# E-01-MB.net
KiCad netlist of a schematic drawn in Altium Designer
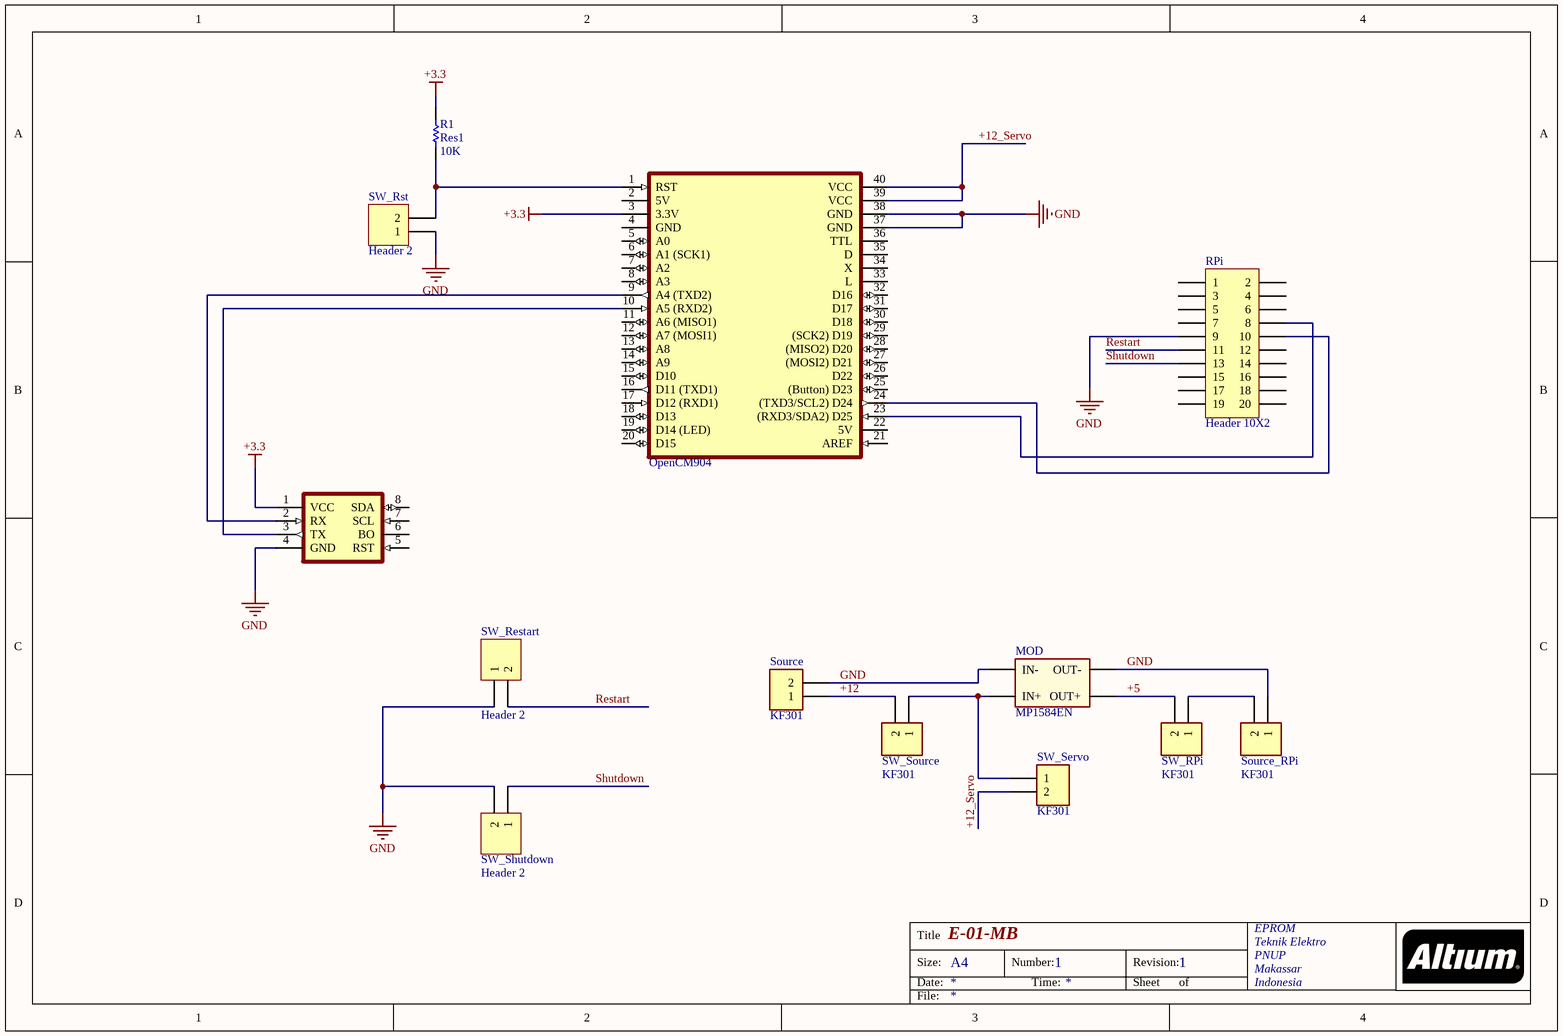
[diagram p0: E-01-MB.SchDoc]

(export (version "E")
  (design (tool "Eeschema 10.0.6"))
  (components
    (comp (ref "GY-Sensor")
      (value "GY25")
      (footprint "GY25")
      (libsource (lib "E-01-MB_Schlib") (part "GY25"))
    )
    (comp (ref "Main")
      (value "OpenCM904")
      (footprint "OpenCM904-DIP40")
      (libsource (lib "E-01-MB_Schlib") (part "OpenCM904"))
    )
    (comp (ref "MOD")
      (value "MP1584EN")
      (footprint "PCBComponent_1")
      (libsource (lib "E-01-PDB_Schlib") (part "MP1584EN"))
    )
    (comp (ref "R1")
      (value "Res1")
      (footprint "AXIAL-0.3")
      (description "Resistor")
      (fields (field (name "ALTIUM_VALUE") "10K") (field (name "PUBLISHER") "Altium Limited"))
      (libsource (lib "Miscellaneous Devices") (part "Res1"))
    )
    (comp (ref "RPi")
      (value "Header 10X2")
      (footprint "HDR2X10")
      (description "Header, 10-Pin, Dual row")
      (fields (field (name "PUBLISHER") "Altium Limited"))
      (libsource (lib "Miscellaneous Connectors") (part "Header 10X2"))
    )
    (comp (ref "Source")
      (value "KF301")
      (footprint "KF301")
      (libsource (lib "E-01-MB_Schlib") (part "KF301"))
    )
    (comp (ref "Source_RPi") (value "KF301") (footprint "KF301") (libsource (lib "") (part "KF301_1")))
    (comp (ref "SW_Restart")
      (value "Header 2")
      (footprint "HDR1X2")
      (description "Header, 2-Pin")
      (fields (field (name "PUBLISHER") "Altium Limited"))
      (libsource (lib "") (part "Header 2_2"))
    )
    (comp (ref "SW_RPi") (value "KF301") (footprint "KF301") (libsource (lib "") (part "KF301_1")))
    (comp (ref "SW_Rst")
      (value "Header 2")
      (footprint "HDR1X2")
      (description "Header, 2-Pin")
      (fields (field (name "PUBLISHER") "Altium Limited"))
      (libsource (lib "Miscellaneous Connectors") (part "Header 2"))
    )
    (comp (ref "SW_Servo") (value "KF301") (footprint "KF301") (libsource (lib "") (part "KF301_2")))
    (comp (ref "SW_Shutdown")
      (value "Header 2")
      (footprint "HDR1X2")
      (description "Header, 2-Pin")
      (fields (field (name "PUBLISHER") "Altium Limited"))
      (libsource (lib "") (part "Header 2_1"))
    )
    (comp (ref "SW_Source") (value "KF301") (footprint "KF301") (libsource (lib "") (part "KF301_1")))
  )
  (nets
    (net (code "1") (name "+3.3") (class "Default")
      (node (ref "GY-Sensor") (pin "1") (pinfunction "VCC_1") (pintype "power_in"))
      (node (ref "Main") (pin "3") (pinfunction "3.3V_3") (pintype "power_in"))
      (node (ref "R1") (pin "2") (pinfunction "2_2") (pintype "passive"))
    )
    (net (code "2") (name "/+5") (class "Default")
      (node (ref "MOD") (pin "4") (pinfunction "OUT+_4") (pintype "power_in"))
      (node (ref "SW_RPi") (pin "2") (pinfunction "2_2") (pintype "passive"))
    )
    (net (code "3") (name "/+12") (class "Default")
      (node (ref "SW_Source") (pin "2") (pinfunction "2_2") (pintype "passive"))
      (node (ref "Source") (pin "1") (pinfunction "1_1") (pintype "passive"))
    )
    (net (code "4") (name "/+12_Servo") (class "Default")
      (node (ref "Main") (pin "39") (pinfunction "VCC_39") (pintype "power_in"))
      (node (ref "Main") (pin "40") (pinfunction "VCC_40") (pintype "power_in"))
      (node (ref "SW_Servo") (pin "2") (pinfunction "2_2") (pintype "passive"))
    )
    (net (code "5") (name "/Restart") (class "Default")
      (node (ref "RPi") (pin "11") (pinfunction "11_11") (pintype "passive"))
      (node (ref "SW_Restart") (pin "2") (pinfunction "2_2") (pintype "passive"))
    )
    (net (code "6") (name "/Shutdown") (class "Default")
      (node (ref "RPi") (pin "13") (pinfunction "13_13") (pintype "passive"))
      (node (ref "SW_Shutdown") (pin "1") (pinfunction "1_1") (pintype "passive"))
    )
    (net (code "7") (name "GND") (class "Default")
      (node (ref "GY-Sensor") (pin "4") (pinfunction "GND_4") (pintype "power_in"))
      (node (ref "MOD") (pin "1") (pinfunction "IN-_1") (pintype "power_in"))
      (node (ref "MOD") (pin "3") (pinfunction "OUT-_3") (pintype "power_in"))
      (node (ref "Main") (pin "37") (pinfunction "GND_37") (pintype "power_in"))
      (node (ref "Main") (pin "38") (pinfunction "GND_38") (pintype "power_in"))
      (node (ref "RPi") (pin "9") (pinfunction "9_9") (pintype "passive"))
      (node (ref "SW_Restart") (pin "1") (pinfunction "1_1") (pintype "passive"))
      (node (ref "SW_Rst") (pin "1") (pinfunction "1_1") (pintype "passive"))
      (node (ref "SW_Shutdown") (pin "2") (pinfunction "2_2") (pintype "passive"))
      (node (ref "Source") (pin "2") (pinfunction "2_2") (pintype "passive"))
      (node (ref "Source_RPi") (pin "1") (pinfunction "1_1") (pintype "passive"))
    )
    (net (code "8") (name "Net-(GY-Sensor-RX)") (class "Default")
      (node (ref "GY-Sensor") (pin "2") (pinfunction "RX_2") (pintype "input"))
      (node (ref "Main") (pin "9") (pinfunction "A4_(TXD2)_9") (pintype "output"))
    )
    (net (code "9") (name "Net-(GY-Sensor-TX)") (class "Default")
      (node (ref "GY-Sensor") (pin "3") (pinfunction "TX_3") (pintype "output"))
      (node (ref "Main") (pin "10") (pinfunction "A5_(RXD2)_10") (pintype "input"))
    )
    (net (code "10") (name "Net-(MOD-IN+)") (class "Default")
      (node (ref "MOD") (pin "2") (pinfunction "IN+_2") (pintype "power_in"))
      (node (ref "SW_Servo") (pin "1") (pinfunction "1_1") (pintype "passive"))
      (node (ref "SW_Source") (pin "1") (pinfunction "1_1") (pintype "passive"))
    )
    (net (code "11") (name "Net-(Main-(RXD3{slash}SDA2)_D25)") (class "Default")
      (node (ref "Main") (pin "23") (pinfunction "(RXD3/SDA2)_D25_23") (pintype "input"))
      (node (ref "RPi") (pin "8") (pinfunction "8_8") (pintype "passive"))
    )
    (net (code "12") (name "Net-(Main-(TXD3{slash}SCL2)_D24)") (class "Default")
      (node (ref "Main") (pin "24") (pinfunction "(TXD3/SCL2)_D24_24") (pintype "output"))
      (node (ref "RPi") (pin "10") (pinfunction "10_10") (pintype "passive"))
    )
    (net (code "13") (name "Net-(Main-RST)") (class "Default")
      (node (ref "Main") (pin "1") (pinfunction "RST_1") (pintype "input"))
      (node (ref "R1") (pin "1") (pinfunction "1_1") (pintype "passive"))
      (node (ref "SW_Rst") (pin "2") (pinfunction "2_2") (pintype "passive"))
    )
    (net (code "14") (name "Net-(SW_RPi-Pad1)") (class "Default")
      (node (ref "SW_RPi") (pin "1") (pinfunction "1_1") (pintype "passive"))
      (node (ref "Source_RPi") (pin "2") (pinfunction "2_2") (pintype "passive"))
    )
    (net (code "15") (name "unconnected-(GY-Sensor-BO-Pad6)") (class "Default")
      (node (ref "GY-Sensor") (pin "6") (pinfunction "BO_6") (pintype "passive"))
    )
    (net (code "16") (name "unconnected-(GY-Sensor-RST-Pad5)") (class "Default")
      (node (ref "GY-Sensor") (pin "5") (pinfunction "RST_5") (pintype "input"))
    )
    (net (code "17") (name "unconnected-(GY-Sensor-SCL-Pad7)") (class "Default")
      (node (ref "GY-Sensor") (pin "7") (pinfunction "SCL_7") (pintype "input"))
    )
    (net (code "18") (name "unconnected-(GY-Sensor-SDA-Pad8)") (class "Default")
      (node (ref "GY-Sensor") (pin "8") (pinfunction "SDA_8") (pintype "bidirectional"))
    )
    (net (code "19") (name "unconnected-(Main-(Button)_D23-Pad25)") (class "Default")
      (node (ref "Main") (pin "25") (pinfunction "(Button)_D23_25") (pintype "bidirectional"))
    )
    (net (code "20") (name "unconnected-(Main-(MISO2)_D20-Pad28)") (class "Default")
      (node (ref "Main") (pin "28") (pinfunction "(MISO2)_D20_28") (pintype "bidirectional"))
    )
    (net (code "21") (name "unconnected-(Main-(MOSI2)_D21-Pad27)") (class "Default")
      (node (ref "Main") (pin "27") (pinfunction "(MOSI2)_D21_27") (pintype "bidirectional"))
    )
    (net (code "22") (name "unconnected-(Main-(SCK2)_D19-Pad29)") (class "Default")
      (node (ref "Main") (pin "29") (pinfunction "(SCK2)_D19_29") (pintype "bidirectional"))
    )
    (net (code "23") (name "unconnected-(Main-5V-Pad2)") (class "Default")
      (node (ref "Main") (pin "2") (pinfunction "5V_2") (pintype "power_in"))
    )
    (net (code "24") (name "unconnected-(Main-5V-Pad22)") (class "Default")
      (node (ref "Main") (pin "22") (pinfunction "5V_22") (pintype "power_in"))
    )
    (net (code "25") (name "unconnected-(Main-A0-Pad5)") (class "Default")
      (node (ref "Main") (pin "5") (pinfunction "A0_5") (pintype "bidirectional"))
    )
    (net (code "26") (name "unconnected-(Main-A1_(SCK1)-Pad6)") (class "Default")
      (node (ref "Main") (pin "6") (pinfunction "A1_(SCK1)_6") (pintype "bidirectional"))
    )
    (net (code "27") (name "unconnected-(Main-A2-Pad7)") (class "Default")
      (node (ref "Main") (pin "7") (pinfunction "A2_7") (pintype "bidirectional"))
    )
    (net (code "28") (name "unconnected-(Main-A3-Pad8)") (class "Default")
      (node (ref "Main") (pin "8") (pinfunction "A3_8") (pintype "bidirectional"))
    )
    (net (code "29") (name "unconnected-(Main-A6_(MISO1)-Pad11)") (class "Default")
      (node (ref "Main") (pin "11") (pinfunction "A6_(MISO1)_11") (pintype "bidirectional"))
    )
    (net (code "30") (name "unconnected-(Main-A7_(MOSI1)-Pad12)") (class "Default")
      (node (ref "Main") (pin "12") (pinfunction "A7_(MOSI1)_12") (pintype "bidirectional"))
    )
    (net (code "31") (name "unconnected-(Main-A8-Pad13)") (class "Default")
      (node (ref "Main") (pin "13") (pinfunction "A8_13") (pintype "bidirectional"))
    )
    (net (code "32") (name "unconnected-(Main-A9-Pad14)") (class "Default")
      (node (ref "Main") (pin "14") (pinfunction "A9_14") (pintype "bidirectional"))
    )
    (net (code "33") (name "unconnected-(Main-AREF-Pad21)") (class "Default")
      (node (ref "Main") (pin "21") (pinfunction "AREF_21") (pintype "input"))
    )
    (net (code "34") (name "unconnected-(Main-D-Pad35)") (class "Default")
      (node (ref "Main") (pin "35") (pinfunction "D_35") (pintype "passive"))
    )
    (net (code "35") (name "unconnected-(Main-D10-Pad15)") (class "Default")
      (node (ref "Main") (pin "15") (pinfunction "D10_15") (pintype "bidirectional"))
    )
    (net (code "36") (name "unconnected-(Main-D11_(TXD1)-Pad16)") (class "Default")
      (node (ref "Main") (pin "16") (pinfunction "D11_(TXD1)_16") (pintype "output"))
    )
    (net (code "37") (name "unconnected-(Main-D12_(RXD1)-Pad17)") (class "Default")
      (node (ref "Main") (pin "17") (pinfunction "D12_(RXD1)_17") (pintype "input"))
    )
    (net (code "38") (name "unconnected-(Main-D13-Pad18)") (class "Default")
      (node (ref "Main") (pin "18") (pinfunction "D13_18") (pintype "bidirectional"))
    )
    (net (code "39") (name "unconnected-(Main-D14_(LED)-Pad19)") (class "Default")
      (node (ref "Main") (pin "19") (pinfunction "D14_(LED)_19") (pintype "bidirectional"))
    )
    (net (code "40") (name "unconnected-(Main-D15-Pad20)") (class "Default")
      (node (ref "Main") (pin "20") (pinfunction "D15_20") (pintype "bidirectional"))
    )
    (net (code "41") (name "unconnected-(Main-D16-Pad32)") (class "Default")
      (node (ref "Main") (pin "32") (pinfunction "D16_32") (pintype "bidirectional"))
    )
    (net (code "42") (name "unconnected-(Main-D17-Pad31)") (class "Default")
      (node (ref "Main") (pin "31") (pinfunction "D17_31") (pintype "bidirectional"))
    )
    (net (code "43") (name "unconnected-(Main-D18-Pad30)") (class "Default")
      (node (ref "Main") (pin "30") (pinfunction "D18_30") (pintype "bidirectional"))
    )
    (net (code "44") (name "unconnected-(Main-D22-Pad26)") (class "Default")
      (node (ref "Main") (pin "26") (pinfunction "D22_26") (pintype "bidirectional"))
    )
    (net (code "45") (name "unconnected-(Main-GND-Pad4)") (class "Default")
      (node (ref "Main") (pin "4") (pinfunction "GND_4") (pintype "power_in"))
    )
    (net (code "46") (name "unconnected-(Main-L-Pad33)") (class "Default")
      (node (ref "Main") (pin "33") (pinfunction "L_33") (pintype "passive"))
    )
    (net (code "47") (name "unconnected-(Main-TTL-Pad36)") (class "Default")
      (node (ref "Main") (pin "36") (pinfunction "TTL_36") (pintype "passive"))
    )
    (net (code "48") (name "unconnected-(Main-X-Pad34)") (class "Default")
      (node (ref "Main") (pin "34") (pinfunction "X_34") (pintype "passive"))
    )
    (net (code "49") (name "unconnected-(RPi-Pad1)") (class "Default")
      (node (ref "RPi") (pin "1") (pinfunction "1_1") (pintype "passive"))
    )
    (net (code "50") (name "unconnected-(RPi-Pad2)") (class "Default")
      (node (ref "RPi") (pin "2") (pinfunction "2_2") (pintype "passive"))
    )
    (net (code "51") (name "unconnected-(RPi-Pad3)") (class "Default")
      (node (ref "RPi") (pin "3") (pinfunction "3_3") (pintype "passive"))
    )
    (net (code "52") (name "unconnected-(RPi-Pad4)") (class "Default")
      (node (ref "RPi") (pin "4") (pinfunction "4_4") (pintype "passive"))
    )
    (net (code "53") (name "unconnected-(RPi-Pad5)") (class "Default")
      (node (ref "RPi") (pin "5") (pinfunction "5_5") (pintype "passive"))
    )
    (net (code "54") (name "unconnected-(RPi-Pad6)") (class "Default")
      (node (ref "RPi") (pin "6") (pinfunction "6_6") (pintype "passive"))
    )
    (net (code "55") (name "unconnected-(RPi-Pad7)") (class "Default")
      (node (ref "RPi") (pin "7") (pinfunction "7_7") (pintype "passive"))
    )
    (net (code "56") (name "unconnected-(RPi-Pad12)") (class "Default")
      (node (ref "RPi") (pin "12") (pinfunction "12_12") (pintype "passive"))
    )
    (net (code "57") (name "unconnected-(RPi-Pad14)") (class "Default")
      (node (ref "RPi") (pin "14") (pinfunction "14_14") (pintype "passive"))
    )
    (net (code "58") (name "unconnected-(RPi-Pad15)") (class "Default")
      (node (ref "RPi") (pin "15") (pinfunction "15_15") (pintype "passive"))
    )
    (net (code "59") (name "unconnected-(RPi-Pad16)") (class "Default")
      (node (ref "RPi") (pin "16") (pinfunction "16_16") (pintype "passive"))
    )
    (net (code "60") (name "unconnected-(RPi-Pad17)") (class "Default")
      (node (ref "RPi") (pin "17") (pinfunction "17_17") (pintype "passive"))
    )
    (net (code "61") (name "unconnected-(RPi-Pad18)") (class "Default")
      (node (ref "RPi") (pin "18") (pinfunction "18_18") (pintype "passive"))
    )
    (net (code "62") (name "unconnected-(RPi-Pad19)") (class "Default")
      (node (ref "RPi") (pin "19") (pinfunction "19_19") (pintype "passive"))
    )
    (net (code "63") (name "unconnected-(RPi-Pad20)") (class "Default")
      (node (ref "RPi") (pin "20") (pinfunction "20_20") (pintype "passive"))
    )
  )
)
